# battery_lcl-charging.net
KiCad netlist of a schematic drawn in Altium Designer
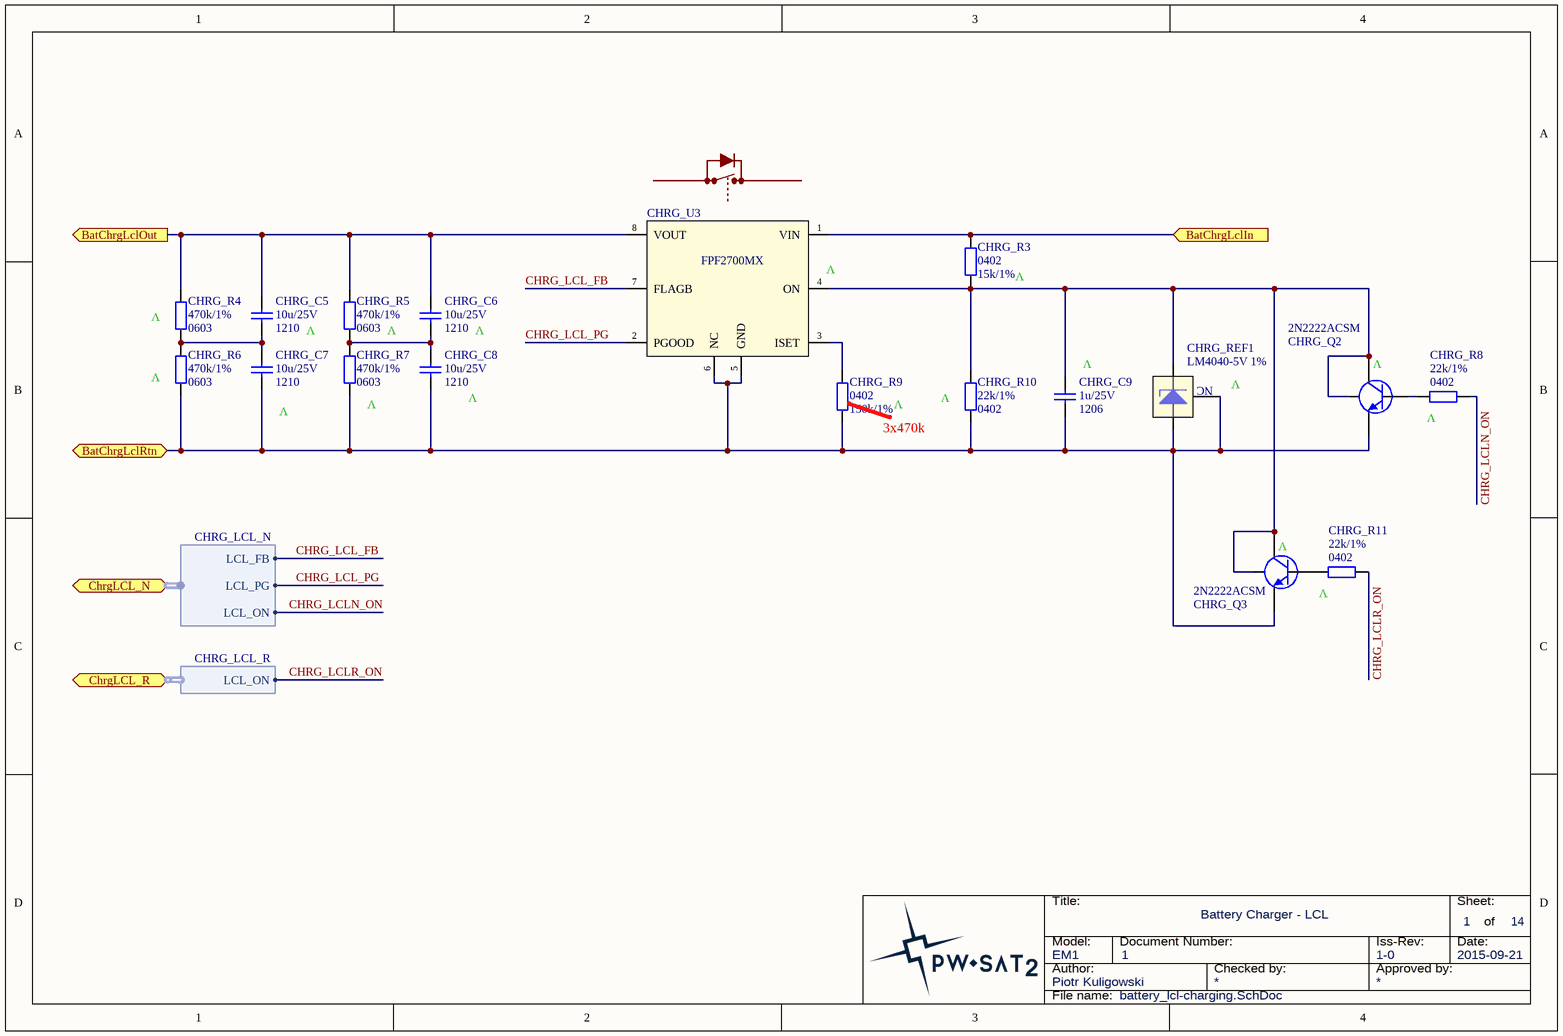
[diagram p0: battery_lcl-charging.SchDoc]

(export (version "E")
  (design (tool "Eeschema 10.0.6"))
  (components
    (comp (ref "CHRG_C5")
      (value "10u/25V")
      (footprint "SMD_Capacitor_1210")
      (description "Ceramic Cap Murata Automotive 10u/25V X7R 1210")
      (fields
        (field (name "MANUFACTURER") "Murata")
        (field (name "MANUFACTURERPARTNUMBER") "GCJ32ER71E106KA12L")
        (field (name "PACKAGE") "1210")
      )
      (libsource (lib "capacitors") (part "Cer_GCJ32ER71E106KA12L"))
    )
    (comp (ref "CHRG_C6")
      (value "10u/25V")
      (footprint "SMD_Capacitor_1210")
      (description "Ceramic Cap Murata Automotive 10u/25V X7R 1210")
      (fields
        (field (name "MANUFACTURER") "Murata")
        (field (name "MANUFACTURERPARTNUMBER") "GCJ32ER71E106KA12L")
        (field (name "PACKAGE") "1210")
      )
      (libsource (lib "capacitors") (part "Cer_GCJ32ER71E106KA12L"))
    )
    (comp (ref "CHRG_C7")
      (value "10u/25V")
      (footprint "SMD_Capacitor_1210")
      (description "Ceramic Cap Murata Automotive 10u/25V X7R 1210")
      (fields
        (field (name "MANUFACTURER") "Murata")
        (field (name "MANUFACTURERPARTNUMBER") "GCJ32ER71E106KA12L")
        (field (name "PACKAGE") "1210")
      )
      (libsource (lib "capacitors") (part "Cer_GCJ32ER71E106KA12L"))
    )
    (comp (ref "CHRG_C8")
      (value "10u/25V")
      (footprint "SMD_Capacitor_1210")
      (description "Ceramic Cap Murata Automotive 10u/25V X7R 1210")
      (fields
        (field (name "MANUFACTURER") "Murata")
        (field (name "MANUFACTURERPARTNUMBER") "GCJ32ER71E106KA12L")
        (field (name "PACKAGE") "1210")
      )
      (libsource (lib "capacitors") (part "Cer_GCJ32ER71E106KA12L"))
    )
    (comp (ref "CHRG_C9")
      (value "1u/25V")
      (footprint "SMD_Capacitor_1206")
      (description "Ceramic Cap Kemet COTS 1u/25V X7R 1206")
      (fields
        (field (name "MANUFACTURERPARTNUMBER") "C1206T105K3RALTU")
        (field (name "MANUFACTURER") "Kemet")
        (field (name "PACKAGE") "1206")
      )
      (libsource (lib "capacitors") (part "Cer_C1206T105K3RALTU"))
    )
    (comp (ref "CHRG_Q2")
      (value "2N2222ACSM")
      (footprint "LCC1-4_BEC")
      (description "Silicon Planar Epitaxial NPN Transistor.")
      (fields (field (name "MANUFACTURER") "Semelab-TT"))
      (libsource (lib "transistors") (part "2N2222ACSM"))
    )
    (comp (ref "CHRG_Q3")
      (value "2N2222ACSM")
      (footprint "LCC1-4_BEC")
      (description "Silicon Planar Epitaxial NPN Transistor.")
      (fields (field (name "MANUFACTURER") "Semelab-TT"))
      (libsource (lib "transistors") (part "2N2222ACSM"))
    )
    (comp (ref "CHRG_R3")
      (value "15k/1%")
      (footprint "SMD_Resistor_0402")
      (description "15k/1% Vishay CRCW 0402 Resistor. 63mW, 100ppm, 50V.")
      (fields
        (field (name "MANUFACTURER") "Vishay")
        (field (name "MANUFACTURERPARTNUMBER") "CRCW040215K0FKxxxx")
        (field (name "PACKAGE") "0402")
      )
      (libsource (lib "resistors") (part "CRCW040215K0FKxxxx"))
    )
    (comp (ref "CHRG_R4")
      (value "470k/1%")
      (footprint "SMD_Resistor_0603")
      (description "470k/1% Vishay CRCW 0603 Resistor. 100mW, 100ppm, 75V.")
      (fields
        (field (name "MANUFACTURER") "Vishay")
        (field (name "MANUFACTURERPARTNUMBER") "CRCW0603470KFKxxxx")
        (field (name "PACKAGE") "0603")
      )
      (libsource (lib "resistors") (part "CRCW0603470KFKxxxx"))
    )
    (comp (ref "CHRG_R5")
      (value "470k/1%")
      (footprint "SMD_Resistor_0603")
      (description "470k/1% Vishay CRCW 0603 Resistor. 100mW, 100ppm, 75V.")
      (fields
        (field (name "MANUFACTURER") "Vishay")
        (field (name "MANUFACTURERPARTNUMBER") "CRCW0603470KFKxxxx")
        (field (name "PACKAGE") "0603")
      )
      (libsource (lib "resistors") (part "CRCW0603470KFKxxxx"))
    )
    (comp (ref "CHRG_R6")
      (value "470k/1%")
      (footprint "SMD_Resistor_0603")
      (description "470k/1% Vishay CRCW 0603 Resistor. 100mW, 100ppm, 75V.")
      (fields
        (field (name "MANUFACTURER") "Vishay")
        (field (name "MANUFACTURERPARTNUMBER") "CRCW0603470KFKxxxx")
        (field (name "PACKAGE") "0603")
      )
      (libsource (lib "resistors") (part "CRCW0603470KFKxxxx"))
    )
    (comp (ref "CHRG_R7")
      (value "470k/1%")
      (footprint "SMD_Resistor_0603")
      (description "470k/1% Vishay CRCW 0603 Resistor. 100mW, 100ppm, 75V.")
      (fields
        (field (name "MANUFACTURER") "Vishay")
        (field (name "MANUFACTURERPARTNUMBER") "CRCW0603470KFKxxxx")
        (field (name "PACKAGE") "0603")
      )
      (libsource (lib "resistors") (part "CRCW0603470KFKxxxx"))
    )
    (comp (ref "CHRG_R8")
      (value "22k/1%")
      (footprint "SMD_Resistor_0402")
      (description "22k/1% Vishay CRCW 0402 Resistor. 63mW, 100ppm, 50V.")
      (fields
        (field (name "MANUFACTURER") "Vishay")
        (field (name "MANUFACTURERPARTNUMBER") "CRCW040222K0FKxxxx")
        (field (name "PACKAGE") "0402")
      )
      (libsource (lib "resistors") (part "CRCW040222K0FKxxxx"))
    )
    (comp (ref "CHRG_R9")
      (value "150k/1%")
      (footprint "SMD_Resistor_0402")
      (description "150k/1% Vishay CRCW 0402 Resistor. 63mW, 100ppm, 50V.")
      (fields
        (field (name "MANUFACTURER") "Vishay")
        (field (name "MANUFACTURERPARTNUMBER") "CRCW0402150KFKxxxx")
        (field (name "PACKAGE") "0402")
      )
      (libsource (lib "resistors") (part "CRCW0402150KFKxxxx"))
    )
    (comp (ref "CHRG_R10")
      (value "22k/1%")
      (footprint "SMD_Resistor_0402")
      (description "22k/1% Vishay CRCW 0402 Resistor. 63mW, 100ppm, 50V.")
      (fields
        (field (name "MANUFACTURER") "Vishay")
        (field (name "MANUFACTURERPARTNUMBER") "CRCW040222K0FKxxxx")
        (field (name "PACKAGE") "0402")
      )
      (libsource (lib "") (part "CRCW040222K0FKxxxx_1"))
    )
    (comp (ref "CHRG_R11")
      (value "22k/1%")
      (footprint "SMD_Resistor_0402")
      (description "22k/1% Vishay CRCW 0402 Resistor. 63mW, 100ppm, 50V.")
      (fields
        (field (name "MANUFACTURER") "Vishay")
        (field (name "MANUFACTURERPARTNUMBER") "CRCW040222K0FKxxxx")
        (field (name "PACKAGE") "0402")
      )
      (libsource (lib "resistors") (part "CRCW040222K0FKxxxx"))
    )
    (comp (ref "CHRG_REF1")
      (value "LM4040-5V 1%")
      (footprint "SOT23-3")
      (description "Shunt V-REF, 5V, 1%, SOT23-3")
      (fields
        (field (name "MANUFACTURER") "Texas Instruments")
        (field (name "MANUFACTURERPARTNUMBER") "LM4040DIM3-5.0")
      )
      (libsource (lib "diodes") (part "LM4040DIM3-5.0"))
    )
    (comp (ref "CHRG_U3")
      (value "FPF2700MX")
      (footprint "SOIC-8-N")
      (description "Adj over-current protection 0.4-2A, Load Switch")
      (fields (field (name "MANUFACTURER") "Fairchild Semiconductor"))
      (libsource (lib "microcircuits") (part "FPF2700MX"))
    )
  )
  (nets
    (net (code "3") (name "/BatChrgLclIn") (class "Default")
      (node (ref "CHRG_R3") (pin "1") (pinfunction "1_1") (pintype "passive"))
      (node (ref "CHRG_U3") (pin "1") (pinfunction "VIN_1") (pintype "passive"))
    )
    (net (code "4") (name "/BatChrgLclOut") (class "Default")
      (node (ref "CHRG_C5") (pin "1") (pinfunction "1_1") (pintype "passive"))
      (node (ref "CHRG_C6") (pin "1") (pinfunction "1_1") (pintype "passive"))
      (node (ref "CHRG_R4") (pin "1") (pinfunction "1_1") (pintype "passive"))
      (node (ref "CHRG_R5") (pin "1") (pinfunction "1_1") (pintype "passive"))
      (node (ref "CHRG_U3") (pin "8") (pinfunction "VOUT_8") (pintype "passive"))
    )
    (net (code "5") (name "/BatChrgLclRtn") (class "Default")
      (node (ref "CHRG_C7") (pin "2") (pinfunction "2_2") (pintype "passive"))
      (node (ref "CHRG_C8") (pin "2") (pinfunction "2_2") (pintype "passive"))
      (node (ref "CHRG_C9") (pin "2") (pinfunction "2_2") (pintype "passive"))
      (node (ref "CHRG_Q2") (pin "E") (pinfunction "E_E") (pintype "passive"))
      (node (ref "CHRG_Q3") (pin "E") (pinfunction "E_E") (pintype "passive"))
      (node (ref "CHRG_R10") (pin "2") (pinfunction "2_2") (pintype "passive"))
      (node (ref "CHRG_R6") (pin "2") (pinfunction "2_2") (pintype "passive"))
      (node (ref "CHRG_R7") (pin "2") (pinfunction "2_2") (pintype "passive"))
      (node (ref "CHRG_R9") (pin "2") (pinfunction "2_2") (pintype "passive"))
      (node (ref "CHRG_REF1") (pin "2") (pinfunction "A_2") (pintype "passive"))
      (node (ref "CHRG_REF1") (pin "3") (pinfunction "NC_3") (pintype "passive"))
      (node (ref "CHRG_U3") (pin "5") (pinfunction "GND_5") (pintype "passive"))
      (node (ref "CHRG_U3") (pin "6") (pinfunction "NC_6") (pintype "passive"))
    )
    (net (code "6") (name "/CHRG_LCLN_ON") (class "Default")
      (node (ref "CHRG_R8") (pin "2") (pinfunction "2_2") (pintype "passive"))
    )
    (net (code "7") (name "/CHRG_LCLR_ON") (class "Default")
      (node (ref "CHRG_R11") (pin "2") (pinfunction "2_2") (pintype "passive"))
    )
    (net (code "8") (name "/CHRG_LCL_FB") (class "Default")
      (node (ref "CHRG_U3") (pin "7") (pinfunction "FLAGB_7") (pintype "passive"))
    )
    (net (code "9") (name "/CHRG_LCL_PG") (class "Default")
      (node (ref "CHRG_U3") (pin "2") (pinfunction "PGOOD_2") (pintype "passive"))
    )
    (net (code "12") (name "Net-(CHRG_C5-Pad2)") (class "Default")
      (node (ref "CHRG_C5") (pin "2") (pinfunction "2_2") (pintype "passive"))
      (node (ref "CHRG_C7") (pin "1") (pinfunction "1_1") (pintype "passive"))
      (node (ref "CHRG_R4") (pin "2") (pinfunction "2_2") (pintype "passive"))
      (node (ref "CHRG_R6") (pin "1") (pinfunction "1_1") (pintype "passive"))
    )
    (net (code "13") (name "Net-(CHRG_C6-Pad2)") (class "Default")
      (node (ref "CHRG_C6") (pin "2") (pinfunction "2_2") (pintype "passive"))
      (node (ref "CHRG_C8") (pin "1") (pinfunction "1_1") (pintype "passive"))
      (node (ref "CHRG_R5") (pin "2") (pinfunction "2_2") (pintype "passive"))
      (node (ref "CHRG_R7") (pin "1") (pinfunction "1_1") (pintype "passive"))
    )
    (net (code "14") (name "Net-(CHRG_Q2-PadB)") (class "Default")
      (node (ref "CHRG_Q2") (pin "B") (pinfunction "B_B") (pintype "passive"))
      (node (ref "CHRG_R8") (pin "1") (pinfunction "1_1") (pintype "passive"))
    )
    (net (code "15") (name "Net-(CHRG_Q3-PadB)") (class "Default")
      (node (ref "CHRG_Q3") (pin "B") (pinfunction "B_B") (pintype "passive"))
      (node (ref "CHRG_R11") (pin "1") (pinfunction "1_1") (pintype "passive"))
    )
    (net (code "16") (name "Net-(CHRG_REF1-K)") (class "Default")
      (node (ref "CHRG_C9") (pin "1") (pinfunction "1_1") (pintype "passive"))
      (node (ref "CHRG_Q2") (pin "C") (pinfunction "C_C") (pintype "passive"))
      (node (ref "CHRG_Q2") (pin "Shield") (pinfunction "Shield_Shield") (pintype "passive"))
      (node (ref "CHRG_Q3") (pin "C") (pinfunction "C_C") (pintype "passive"))
      (node (ref "CHRG_Q3") (pin "Shield") (pinfunction "Shield_Shield") (pintype "passive"))
      (node (ref "CHRG_R10") (pin "1") (pinfunction "1_1") (pintype "passive"))
      (node (ref "CHRG_R3") (pin "2") (pinfunction "2_2") (pintype "passive"))
      (node (ref "CHRG_REF1") (pin "1") (pinfunction "K_1") (pintype "passive"))
      (node (ref "CHRG_U3") (pin "4") (pinfunction "ON_4") (pintype "passive"))
    )
    (net (code "17") (name "Net-(CHRG_U3-ISET)") (class "Default")
      (node (ref "CHRG_R9") (pin "1") (pinfunction "1_1") (pintype "passive"))
      (node (ref "CHRG_U3") (pin "3") (pinfunction "ISET_3") (pintype "passive"))
    )
  )
)
